# Power_Input_and_Buck_Convertors.net
KiCad netlist of a schematic drawn in Altium Designer
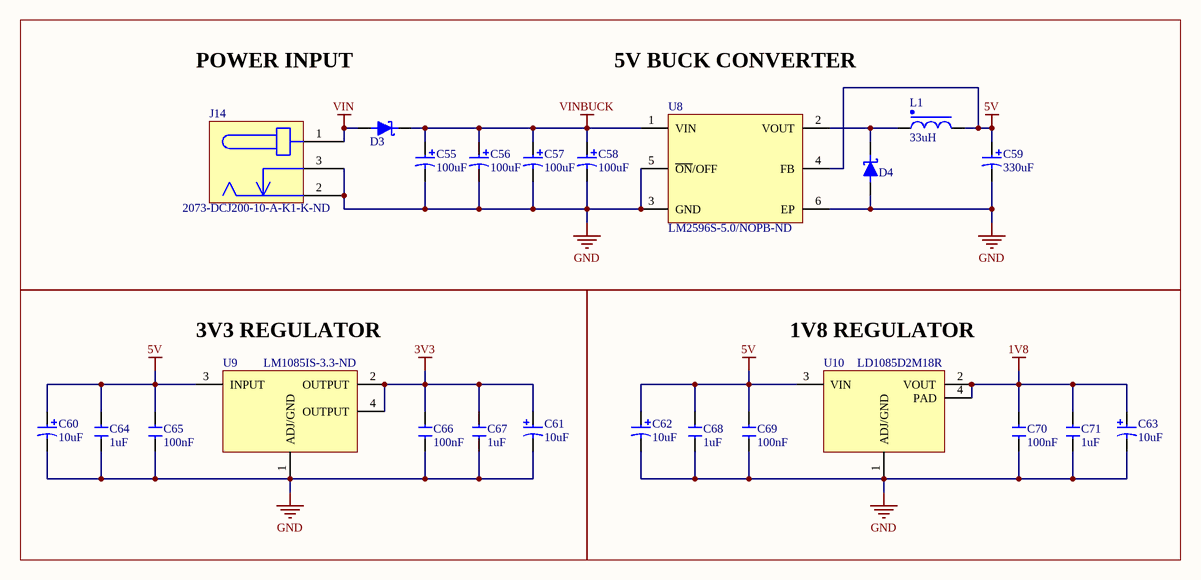
[diagram p0: Power Input and Buck Convertors.SchDoc]

(export (version "E")
  (design (tool "Eeschema 10.0.6"))
  (components
    (comp (ref "C55")
      (value "CAP_100uF_%20_25V_ALUM_SMD")
      (footprint "RADIAL-2_6.3MMX7.7MM")
      (description "CAP.EL.100uF 25V 6.3x7.7 105C 5000HRS SMD")
      (fields
        (field (name "TOLERANCE") "20%")
        (field (name "MANUFACTURER") "SAMYOUNG")
        (field (name "CAPACITANCE") "100uF")
      )
      (libsource (lib "Main Schematic Library") (part "CAP_100uF_%20_25V_ALUM_SMD"))
    )
    (comp (ref "C56")
      (value "CAP_100uF_%20_25V_ALUM_SMD")
      (footprint "RADIAL-2_6.3MMX7.7MM")
      (description "CAP.EL.100uF 25V 6.3x7.7 105C 5000HRS SMD")
      (fields
        (field (name "TOLERANCE") "20%")
        (field (name "MANUFACTURER") "SAMYOUNG")
        (field (name "CAPACITANCE") "100uF")
      )
      (libsource (lib "Main Schematic Library") (part "CAP_100uF_%20_25V_ALUM_SMD"))
    )
    (comp (ref "C57")
      (value "CAP_100uF_%20_25V_ALUM_SMD")
      (footprint "RADIAL-2_6.3MMX7.7MM")
      (description "CAP.EL.100uF 25V 6.3x7.7 105C 5000HRS SMD")
      (fields
        (field (name "TOLERANCE") "20%")
        (field (name "MANUFACTURER") "SAMYOUNG")
        (field (name "CAPACITANCE") "100uF")
      )
      (libsource (lib "Main Schematic Library") (part "CAP_100uF_%20_25V_ALUM_SMD"))
    )
    (comp (ref "C58")
      (value "CAP_100uF_%20_25V_ALUM_SMD")
      (footprint "RADIAL-2_6.3MMX7.7MM")
      (description "CAP.EL.100uF 25V 6.3x7.7 105C 5000HRS SMD")
      (fields
        (field (name "TOLERANCE") "20%")
        (field (name "MANUFACTURER") "SAMYOUNG")
        (field (name "CAPACITANCE") "100uF")
      )
      (libsource (lib "Main Schematic Library") (part "CAP_100uF_%20_25V_ALUM_SMD"))
    )
    (comp (ref "C59")
      (value "CAP_330uF_%20_25V_ALUM_SMD")
      (footprint "RADIAL-2_8MMX10MM")
      (description "CAP.EL.330uF 25V 8x10 105C 5000Hrs SMD AECQ-200")
      (fields
        (field (name "TOLERANCE") "20%")
        (field (name "MANUFACTURER") "SAMYOUNG")
        (field (name "CAPACITANCE") "330uF")
      )
      (libsource (lib "Main Schematic Library") (part "CAP_330uF_%20_25V_ALUM_SMD"))
    )
    (comp (ref "C60")
      (value "CAP_10uF_10%_1206_10V_TANT")
      (footprint "1206_TANT_CAP")
      (description "Cap Tant Solid 10uF 10V A CASE 10% (3.2 X 1.6 X 1.6mm) Inward L SMD 3216-18 3 Ohm 125C T/R")
      (fields
        (field (name "MANUFACTURER") "Kyocera AVX")
        (field (name "MANUFACTURER PART NUMBER") "TAJA106K010SNJ")
        (field (name "CAPACITANCE") "10uF")
      )
      (libsource (lib "Main Schematic Library") (part "CAP_10uF_10%_1206_10V_TANT"))
    )
    (comp (ref "C61")
      (value "CAP_10uF_10%_1206_10V_TANT")
      (footprint "1206_TANT_CAP")
      (description "Cap Tant Solid 10uF 10V A CASE 10% (3.2 X 1.6 X 1.6mm) Inward L SMD 3216-18 3 Ohm 125C T/R")
      (fields
        (field (name "MANUFACTURER") "Kyocera AVX")
        (field (name "MANUFACTURER PART NUMBER") "TAJA106K010SNJ")
        (field (name "CAPACITANCE") "10uF")
      )
      (libsource (lib "Main Schematic Library") (part "CAP_10uF_10%_1206_10V_TANT"))
    )
    (comp (ref "C62")
      (value "CAP_10uF_10%_1206_10V_TANT")
      (footprint "1206_TANT_CAP")
      (description "Cap Tant Solid 10uF 10V A CASE 10% (3.2 X 1.6 X 1.6mm) Inward L SMD 3216-18 3 Ohm 125C T/R")
      (fields
        (field (name "MANUFACTURER") "Kyocera AVX")
        (field (name "MANUFACTURER PART NUMBER") "TAJA106K010SNJ")
        (field (name "CAPACITANCE") "10uF")
      )
      (libsource (lib "Main Schematic Library") (part "CAP_10uF_10%_1206_10V_TANT"))
    )
    (comp (ref "C63")
      (value "CAP_10uF_10%_1206_10V_TANT")
      (footprint "1206_TANT_CAP")
      (description "Cap Tant Solid 10uF 10V A CASE 10% (3.2 X 1.6 X 1.6mm) Inward L SMD 3216-18 3 Ohm 125C T/R")
      (fields
        (field (name "MANUFACTURER") "Kyocera AVX")
        (field (name "MANUFACTURER PART NUMBER") "TAJA106K010SNJ")
        (field (name "CAPACITANCE") "10uF")
      )
      (libsource (lib "Main Schematic Library") (part "CAP_10uF_10%_1206_10V_TANT"))
    )
    (comp (ref "C64")
      (value "1uF")
      (footprint "0805_CAP")
      (description "陶瓷电容 1uF(105) 1uF ±10% 25V 0805")
      (fields
        (field (name "MANUFACTURER") "Samsung")
        (field (name "MANUFACTURER PART NUMBER") "CL21B105KAFNNNG")
      )
      (libsource (lib "Main Schematic Library") (part "CAP_1uF_%10_25V_0805_X7R_CER"))
    )
    (comp (ref "C65")
      (value "CAP_0.1uF_%20_50V_0805_X7R_CER")
      (footprint "0805_CAP")
      (description "Cap Ceramic 0.1uF 50V X7R 20% SMD 0805 125C Paper T/R")
      (fields
        (field (name "MANUFACTURER") "KEMET")
        (field (name "MANUFACTURER PART NUMBER") "C0805C104M5RACTU")
        (field (name "CAPACITANCE") "100nF")
      )
      (libsource (lib "Main Schematic Library") (part "CAP_0.1uF_%20_50V_0805_X7R_CER"))
    )
    (comp (ref "C66")
      (value "CAP_0.1uF_%20_50V_0805_X7R_CER")
      (footprint "0805_CAP")
      (description "Cap Ceramic 0.1uF 50V X7R 20% SMD 0805 125C Paper T/R")
      (fields
        (field (name "MANUFACTURER") "KEMET")
        (field (name "MANUFACTURER PART NUMBER") "C0805C104M5RACTU")
        (field (name "CAPACITANCE") "100nF")
      )
      (libsource (lib "Main Schematic Library") (part "CAP_0.1uF_%20_50V_0805_X7R_CER"))
    )
    (comp (ref "C67")
      (value "1uF")
      (footprint "0805_CAP")
      (description "陶瓷电容 1uF(105) 1uF ±10% 25V 0805")
      (fields
        (field (name "MANUFACTURER") "Samsung")
        (field (name "MANUFACTURER PART NUMBER") "CL21B105KAFNNNG")
      )
      (libsource (lib "Main Schematic Library") (part "CAP_1uF_%10_25V_0805_X7R_CER"))
    )
    (comp (ref "C68")
      (value "1uF")
      (footprint "0805_CAP")
      (description "陶瓷电容 1uF(105) 1uF ±10% 25V 0805")
      (fields
        (field (name "MANUFACTURER") "Samsung")
        (field (name "MANUFACTURER PART NUMBER") "CL21B105KAFNNNG")
      )
      (libsource (lib "Main Schematic Library") (part "CAP_1uF_%10_25V_0805_X7R_CER"))
    )
    (comp (ref "C69")
      (value "CAP_0.1uF_%20_50V_0805_X7R_CER")
      (footprint "0805_CAP")
      (description "Cap Ceramic 0.1uF 50V X7R 20% SMD 0805 125C Paper T/R")
      (fields
        (field (name "MANUFACTURER") "KEMET")
        (field (name "MANUFACTURER PART NUMBER") "C0805C104M5RACTU")
        (field (name "CAPACITANCE") "100nF")
      )
      (libsource (lib "Main Schematic Library") (part "CAP_0.1uF_%20_50V_0805_X7R_CER"))
    )
    (comp (ref "C70")
      (value "CAP_0.1uF_%20_50V_0805_X7R_CER")
      (footprint "0805_CAP")
      (description "Cap Ceramic 0.1uF 50V X7R 20% SMD 0805 125C Paper T/R")
      (fields
        (field (name "MANUFACTURER") "KEMET")
        (field (name "MANUFACTURER PART NUMBER") "C0805C104M5RACTU")
        (field (name "CAPACITANCE") "100nF")
      )
      (libsource (lib "Main Schematic Library") (part "CAP_0.1uF_%20_50V_0805_X7R_CER"))
    )
    (comp (ref "C71")
      (value "1uF")
      (footprint "0805_CAP")
      (description "陶瓷电容 1uF(105) 1uF ±10% 25V 0805")
      (fields
        (field (name "MANUFACTURER") "Samsung")
        (field (name "MANUFACTURER PART NUMBER") "CL21B105KAFNNNG")
      )
      (libsource (lib "Main Schematic Library") (part "CAP_1uF_%10_25V_0805_X7R_CER"))
    )
    (comp (ref "D3")
      (value "D1FH3/5053")
      (footprint "DIOM5226X220N_D1FH3/5053")
      (description "Schottky-diode 3A 30V 1F")
      (fields (field (name "MANUFACTURER") "Shindengen"))
      (libsource (lib "Main Schematic Library") (part "DIODE_SCHOTTKY_30V_3A_DO214AC/SMA_SMT"))
    )
    (comp (ref "D4")
      (value "DIODE_SCHOTTKY_60V_3A_DO-214AC/SMA")
      (footprint "DIOM5226X220N-SMA")
      (description "DIODE SCHOTTKY 3A 60V DO-214AC SMA")
      (fields (field (name "MANUFACTURER PART NUMBER") "SS36-JQ"))
      (libsource (lib "Main Schematic Library") (part "DIODE_SCHOTTKY_60V_3A_DO-214AC/SMA"))
    )
    (comp (ref "J14")
      (value "CON_JACK_POWER_PCB TYPE_2MM_KLS")
      (footprint "DC_POWER_JACK_2MM")
      (description "DCJ200 Series 20 V 5 A Horizontal PCB Mount Jack Power Jack")
      (fields
        (field (name "MANUFACTURER") "Global Connector Technology")
        (field (name "MANUFACTURER PART NUMBER") "DCJ200-10-A-K1-K")
        (field (name "SUPPLIER PART NUMBER 1") "2073-DCJ200-10-A-K1-K-ND")
      )
      (libsource (lib "Main Schematic Library") (part "CON_JACK_POWER_PCB TYPE_2MM_KLS"))
    )
    (comp (ref "L1")
      (value "IND_33uH_5A_65mOHM_12X12MM_SMD")
      (footprint "INDP120120X800N")
      (description "INDUCTOR POWER 33UH 12X12MM SMD")
      (fields
        (field (name "MANUFACTURER") "CORE MASTER")
        (field (name "MANUFACTURER PART NUMBER") "SRI1207-330M")
        (field (name "INDUCTANCE") "33uH")
      )
      (libsource (lib "Main Schematic Library") (part "IND_33uH_5A_65mOHM_12X12MM_SMD"))
    )
    (comp (ref "U8")
      (value "PMIC_LM2596S-5.0/NOPB")
      (footprint "TO170P1524X483-6N")
      (description "SIMPLE SWITCHER® 4.5V to 40V, 3A Low Component Count Step-Down Regulator 5-DDPAK/TO-263")
      (fields
        (field (name "MANUFACTURER") "TI National Semiconductor")
        (field (name "MANUFACTURER PART NUMBER") "LM2596S-5.0/NOPB")
        (field (name "SUPPLIER PART NUMBER 1") "LM2596S-5.0/NOPB-ND")
      )
      (libsource (lib "Main Schematic Library") (part "PMIC_LM2596S-5.0/NOPB"))
    )
    (comp (ref "U9")
      (value "PMIC_LIN REG_LM1085IS-3.3")
      (footprint "TO254P1524X483-4N")
      (description "3-A, 29-V, linear voltage regulator 3-DDPAK/TO-263 -40 to 125")
      (fields
        (field (name "MANUFACTURER") "TI National Semiconductor")
        (field (name "MANUFACTURER PART NUMBER") "LM1085IS-3.3")
        (field (name "SUPPLIER PART NUMBER 1") "LM1085IS-3.3-ND")
      )
      (libsource (lib "Main Schematic Library") (part "PMIC_LIN REG_LM1085IS-3.3"))
    )
    (comp (ref "U10")
      (value "LD1085D2M18R")
      (footprint "DPAK254P1542X460-4N")
      (description "LDO Regulator Pos 1.8V 3A Automotive 4-Pin(3+Tab) D2PAK/A T/R")
      (fields (field (name "MANUFACTURER") "STMicroelectronics"))
      (libsource (lib "Main Schematic Library") (part "PMIC_LDO_LD1085D2M18R"))
    )
  )
  (nets
    (net (code "1") (name "1V8") (class "Default")
      (node (ref "C63") (pin "1") (pinfunction "1_1") (pintype "passive"))
      (node (ref "C70") (pin "2") (pinfunction "2_2") (pintype "passive"))
      (node (ref "C71") (pin "2") (pinfunction "2_2") (pintype "passive"))
      (node (ref "U10") (pin "2") (pinfunction "VOUT_2") (pintype "passive"))
      (node (ref "U10") (pin "4") (pinfunction "PAD_4") (pintype "passive"))
    )
    (net (code "2") (name "3V3") (class "Default")
      (node (ref "C61") (pin "1") (pinfunction "1_1") (pintype "passive"))
      (node (ref "C66") (pin "2") (pinfunction "2_2") (pintype "passive"))
      (node (ref "C67") (pin "2") (pinfunction "2_2") (pintype "passive"))
      (node (ref "U9") (pin "2") (pinfunction "OUTPUT_2") (pintype "passive"))
      (node (ref "U9") (pin "4") (pinfunction "OUTPUT_4") (pintype "passive"))
    )
    (net (code "3") (name "5V") (class "Default")
      (node (ref "C59") (pin "1") (pinfunction "1_1") (pintype "passive"))
      (node (ref "C60") (pin "1") (pinfunction "1_1") (pintype "passive"))
      (node (ref "C62") (pin "1") (pinfunction "1_1") (pintype "passive"))
      (node (ref "C64") (pin "2") (pinfunction "2_2") (pintype "passive"))
      (node (ref "C65") (pin "2") (pinfunction "2_2") (pintype "passive"))
      (node (ref "C68") (pin "2") (pinfunction "2_2") (pintype "passive"))
      (node (ref "C69") (pin "2") (pinfunction "2_2") (pintype "passive"))
      (node (ref "L1") (pin "2") (pinfunction "2_2") (pintype "passive"))
      (node (ref "U10") (pin "3") (pinfunction "VIN_3") (pintype "passive"))
      (node (ref "U8") (pin "4") (pinfunction "FB_4") (pintype "passive"))
      (node (ref "U9") (pin "3") (pinfunction "INPUT_3") (pintype "passive"))
    )
    (net (code "4") (name "GND") (class "Default")
      (node (ref "C55") (pin "2") (pinfunction "2_2") (pintype "passive"))
      (node (ref "C56") (pin "2") (pinfunction "2_2") (pintype "passive"))
      (node (ref "C57") (pin "2") (pinfunction "2_2") (pintype "passive"))
      (node (ref "C58") (pin "2") (pinfunction "2_2") (pintype "passive"))
      (node (ref "C59") (pin "2") (pinfunction "2_2") (pintype "passive"))
      (node (ref "C60") (pin "2") (pinfunction "2_2") (pintype "passive"))
      (node (ref "C61") (pin "2") (pinfunction "2_2") (pintype "passive"))
      (node (ref "C62") (pin "2") (pinfunction "2_2") (pintype "passive"))
      (node (ref "C63") (pin "2") (pinfunction "2_2") (pintype "passive"))
      (node (ref "C64") (pin "1") (pinfunction "1_1") (pintype "passive"))
      (node (ref "C65") (pin "1") (pinfunction "1_1") (pintype "passive"))
      (node (ref "C66") (pin "1") (pinfunction "1_1") (pintype "passive"))
      (node (ref "C67") (pin "1") (pinfunction "1_1") (pintype "passive"))
      (node (ref "C68") (pin "1") (pinfunction "1_1") (pintype "passive"))
      (node (ref "C69") (pin "1") (pinfunction "1_1") (pintype "passive"))
      (node (ref "C70") (pin "1") (pinfunction "1_1") (pintype "passive"))
      (node (ref "C71") (pin "1") (pinfunction "1_1") (pintype "passive"))
      (node (ref "D4") (pin "2") (pinfunction "ANODE_2") (pintype "passive"))
      (node (ref "J14") (pin "2") (pinfunction "GND_2") (pintype "passive"))
      (node (ref "J14") (pin "3") (pinfunction "GND_3") (pintype "passive"))
      (node (ref "U10") (pin "1") (pinfunction "ADJ/GND_1") (pintype "passive"))
      (node (ref "U8") (pin "3") (pinfunction "GND_3") (pintype "passive"))
      (node (ref "U8") (pin "5") (pinfunction "~{ON}/OFF_5") (pintype "passive"))
      (node (ref "U8") (pin "6") (pinfunction "EP_6") (pintype "passive"))
      (node (ref "U9") (pin "1") (pinfunction "ADJ/GND_1") (pintype "passive"))
    )
    (net (code "5") (name "Net-(D4-CATHODE)") (class "Default")
      (node (ref "D4") (pin "1") (pinfunction "CATHODE_1") (pintype "passive"))
      (node (ref "L1") (pin "1") (pinfunction "1_1") (pintype "passive"))
      (node (ref "U8") (pin "2") (pinfunction "VOUT_2") (pintype "passive"))
    )
    (net (code "6") (name "VIN") (class "Default")
      (node (ref "D3") (pin "2") (pinfunction "ANODE_2") (pintype "passive"))
      (node (ref "J14") (pin "1") (pinfunction "VIN_1") (pintype "passive"))
    )
    (net (code "7") (name "VINBUCK") (class "Default")
      (node (ref "C55") (pin "1") (pinfunction "1_1") (pintype "passive"))
      (node (ref "C56") (pin "1") (pinfunction "1_1") (pintype "passive"))
      (node (ref "C57") (pin "1") (pinfunction "1_1") (pintype "passive"))
      (node (ref "C58") (pin "1") (pinfunction "1_1") (pintype "passive"))
      (node (ref "D3") (pin "1") (pinfunction "CATHODE_1") (pintype "passive"))
      (node (ref "U8") (pin "1") (pinfunction "VIN_1") (pintype "passive"))
    )
  )
)
